# ap33772s.net
KiCad netlist of a schematic drawn in Altium Designer
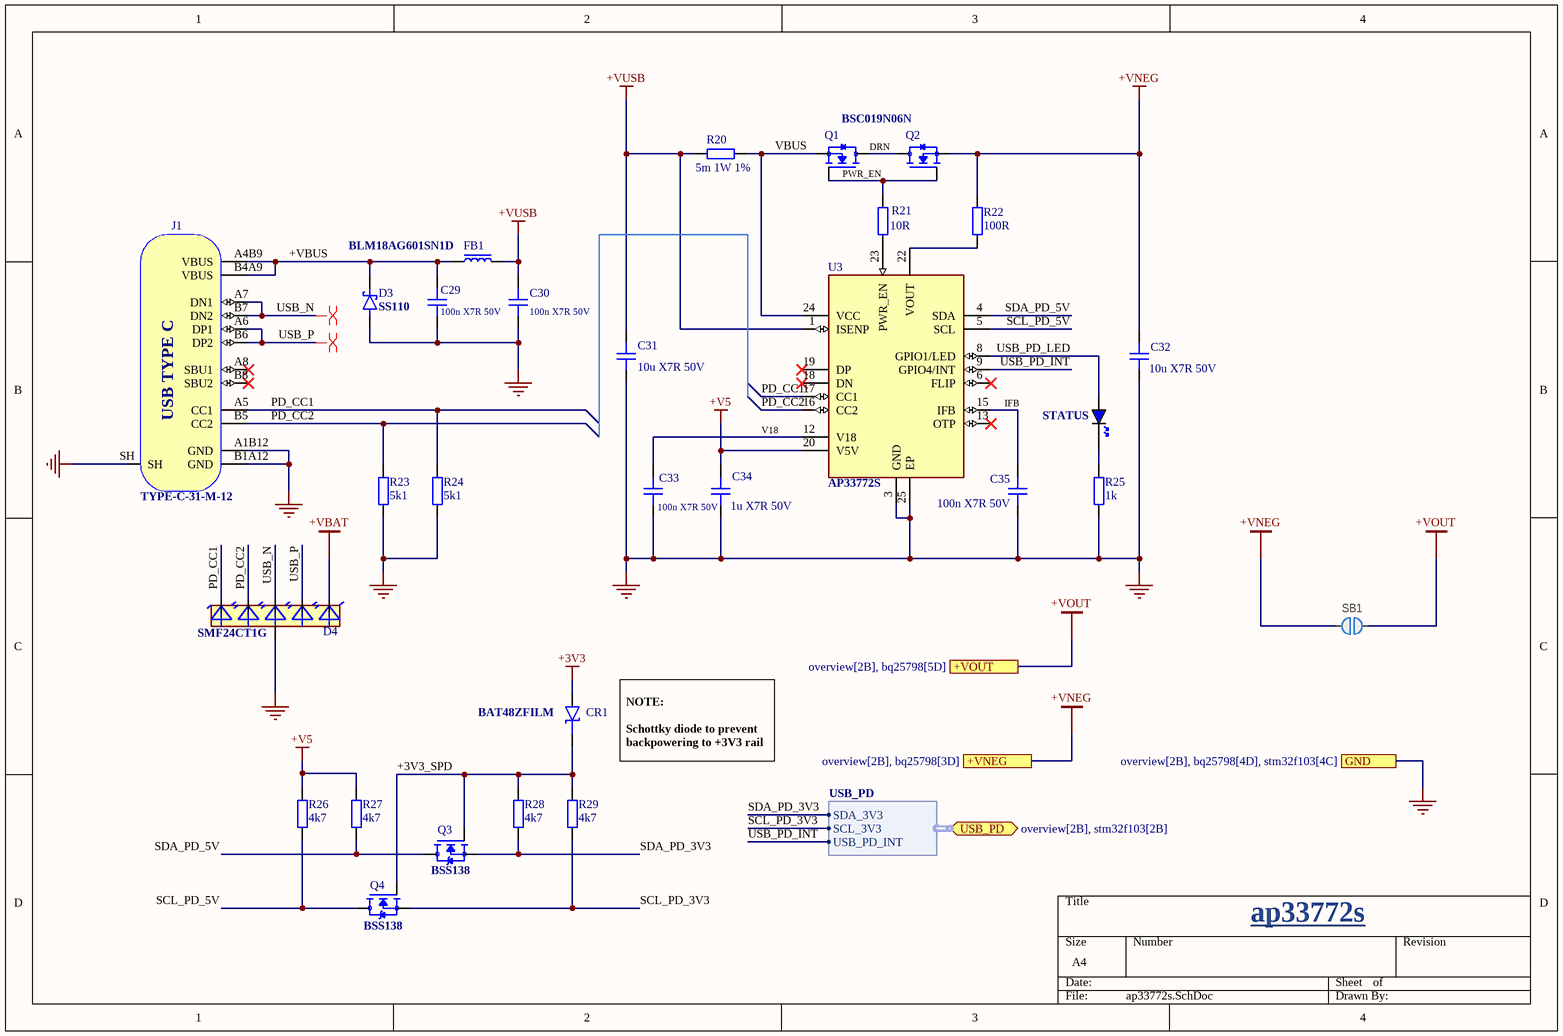
[diagram p0: ap33772s.SchDoc]

(export (version "E")
  (design (tool "Eeschema 10.0.6"))
  (components
    (comp (ref "C29")
      (value "100n X7R 50V")
      (footprint "CAP_0603")
      (description "Capacitor SMD 0603")
      (libsource (lib "Sch_Lib") (part "CAP_0603"))
    )
    (comp (ref "C30")
      (value "100n X7R 50V")
      (footprint "CAP_0603")
      (description "Capacitor SMD 0603")
      (libsource (lib "Sch_Lib") (part "CAP_0603"))
    )
    (comp (ref "C31")
      (value "10u X7R 50V")
      (footprint "CAP_1210")
      (description "Capacitor SMD 1210")
      (libsource (lib "Sch_Lib") (part "CAP_1210"))
    )
    (comp (ref "C32")
      (value "10u X7R 50V")
      (footprint "CAP_1210")
      (description "Capacitor SMD 1210")
      (libsource (lib "Sch_Lib") (part "CAP_1210"))
    )
    (comp (ref "C33")
      (value "100n X7R 50V")
      (footprint "CAP_0603")
      (description "Capacitor SMD 0603")
      (libsource (lib "Sch_Lib") (part "CAP_0603"))
    )
    (comp (ref "C34")
      (value "1u X7R 50V")
      (footprint "CAP_0603")
      (description "Capacitor SMD 0603")
      (libsource (lib "Sch_Lib") (part "CAP_0603"))
    )
    (comp (ref "C35")
      (value "100n X7R 50V")
      (footprint "CAP_0603")
      (description "Capacitor SMD 0603")
      (libsource (lib "Sch_Lib") (part "CAP_0603"))
    )
    (comp (ref "CR1")
      (value "BAT48ZFILM")
      (footprint "*SOD-123_STM")
      (description "Diode Schottky 40 V 350mA (DC) Surface Mount SOD-123")
      (fields (field (name "MF") "STMicroelectronics"))
      (libsource (lib "Sch_Lib") (part "BAT48ZFILM"))
    )
    (comp (ref "D3")
      (value "SS110")
      (footprint "DIOM4325X250N")
      (description "1A, 100V, Schottky Rectifier")
      (fields (field (name "MF") "Taiwan Semiconductor"))
      (libsource (lib "Sch_Lib") (part "SS110"))
    )
    (comp (ref "D4")
      (value "SMF24CT1G")
      (footprint "SOT65P210X110-6N")
      (description "Quint Uni-Directional TVS Diode, 100W, 6-Pin SC-88 ¦ ON Semiconductor SMF24CT1G")
      (fields (field (name "MP") "SMF05C") (field (name "MF") "ProTek Devices"))
      (libsource (lib "Sch_Lib") (part "SMF24CT1G"))
    )
    (comp (ref "FB1")
      (value "BLM18AG601SN1D")
      (footprint "FB_0603")
      (description "Ferrite Bead SMD 0603")
      (libsource (lib "Sch_Lib") (part "FB_0603"))
    )
    (comp (ref "J1")
      (value "TYPE-C-31-M-12")
      (footprint "TYPE-C-31-M-12")
      (description "USB Type C Connector Horizontal SMT")
      (fields (field (name "MANUFACTURER") "Koren Hroparts"))
      (libsource (lib "Sch_Lib") (part "TYPE-C-31-M-12"))
    )
    (comp (ref "Q1")
      (value "BSC019N06N")
      (footprint "BSC014N04LSIATMA1")
      (description "N-Channel 60 V 100A (Ta) 136W (Ta) Surface Mount PG-TDSON-8 FL")
      (fields (field (name "MF") "Infineon") (field (name "MP") "IPD122N10N3 G"))
      (libsource (lib "Sch_Lib") (part "BSC019N06N"))
    )
    (comp (ref "Q2")
      (value "BSC019N06N")
      (footprint "BSC014N04LSIATMA1")
      (description "N-Channel 60 V 100A (Ta) 136W (Ta) Surface Mount PG-TDSON-8 FL")
      (fields (field (name "MF") "Infineon") (field (name "MP") "IPD122N10N3 G"))
      (libsource (lib "Sch_Lib") (part "BSC019N06N"))
    )
    (comp (ref "Q3")
      (value "BSS138")
      (footprint "SOT95P240X111-3N")
      (description "N-Channel 50 V 220mA (Ta) 350mW (Ta) Surface Mount SOT-23-3")
      (fields (field (name "MF") "onsemi"))
      (libsource (lib "Sch_Lib") (part "BSS138"))
    )
    (comp (ref "Q4")
      (value "BSS138")
      (footprint "SOT95P240X111-3N")
      (description "N-Channel 50 V 220mA (Ta) 350mW (Ta) Surface Mount SOT-23-3")
      (fields (field (name "MF") "onsemi"))
      (libsource (lib "Sch_Lib") (part "BSS138"))
    )
    (comp (ref "R20")
      (value "5m 1W 1%")
      (footprint "RES_1206")
      (description "Resistor SMD 1206")
      (libsource (lib "Sch_Lib") (part "RES_1206"))
    )
    (comp (ref "R21")
      (value "10R")
      (footprint "RES_0603")
      (description "Resistor SMD 0603")
      (libsource (lib "Sch_Lib") (part "RES_0603"))
    )
    (comp (ref "R22")
      (value "100R")
      (footprint "RES_0603")
      (description "Resistor SMD 0603")
      (libsource (lib "Sch_Lib") (part "RES_0603"))
    )
    (comp (ref "R23")
      (value "5k1")
      (footprint "RES_0603")
      (description "Resistor SMD 0603")
      (libsource (lib "Schematic-Lib-PhilsLab") (part "RES_0603"))
    )
    (comp (ref "R24")
      (value "5k1")
      (footprint "RES_0603")
      (description "Resistor SMD 0603")
      (libsource (lib "Schematic-Lib-PhilsLab") (part "RES_0603"))
    )
    (comp (ref "R25")
      (value "1k")
      (footprint "RES_0603")
      (description "Resistor SMD 0603")
      (libsource (lib "Schematic-Lib-PhilsLab") (part "RES_0603"))
    )
    (comp (ref "R26")
      (value "4k7")
      (footprint "RES_0603")
      (description "Resistor SMD 0603")
      (libsource (lib "Sch_Lib") (part "RES_0603"))
    )
    (comp (ref "R27")
      (value "4k7")
      (footprint "RES_0603")
      (description "Resistor SMD 0603")
      (libsource (lib "Sch_Lib") (part "RES_0603"))
    )
    (comp (ref "R28")
      (value "4k7")
      (footprint "RES_0603")
      (description "Resistor SMD 0603")
      (libsource (lib "Sch_Lib") (part "RES_0603"))
    )
    (comp (ref "R29")
      (value "4k7")
      (footprint "RES_0603")
      (description "Resistor SMD 0603")
      (libsource (lib "Sch_Lib") (part "RES_0603"))
    )
    (comp (ref "SB1")
      (value "Solderbridge")
      (footprint "Solderbridge")
      (fields (field (name "MANUFACTURER") "N.A.") (field (name "AUTHOR") "rsk"))
      (libsource (lib "Sch_Lib") (part "Solderbridge"))
    )
    (comp (ref "STATUS")
      (value "BLUE")
      (footprint "LED_0603_BLUE")
      (description "LED 0603 BLUE SMD")
      (libsource (lib "Schematic-Lib-PhilsLab") (part "LED_0603_BLUE"))
    )
    (comp (ref "U3")
      (value "AP33772S")
      (footprint "IC_AP33772S")
      (description "USB Controller, PD Sink USB 3.0 USB Interface W-QFN4040-24 (Type A1)")
      (fields (field (name "MF") "Diodes Incorporated") (field (name "MP") "AP33771DKZ-13"))
      (libsource (lib "Sch_Lib") (part "AP33772S"))
    )
  )
  (nets
    (net (code "2") (name "+3V3") (class "Default")
      (node (ref "CR1") (pin "2") (pinfunction "2_2") (pintype "passive"))
    )
    (net (code "3") (name "+V5") (class "Default")
      (node (ref "C34") (pin "2") (pinfunction "2_2") (pintype "passive"))
      (node (ref "R26") (pin "2") (pinfunction "2_2") (pintype "passive"))
      (node (ref "R27") (pin "2") (pinfunction "2_2") (pintype "passive"))
      (node (ref "U3") (pin "20") (pinfunction "V5V_20") (pintype "power_in"))
    )
    (net (code "4") (name "+VBAT") (class "Default")
      (node (ref "D4") (pin "6") (pinfunction "C5_6") (pintype "passive"))
    )
    (net (code "5") (name "+VNEG") (class "Default")
      (node (ref "C32") (pin "2") (pinfunction "2_2") (pintype "passive"))
      (node (ref "Q2") (pin "1") (pinfunction "S_1") (pintype "passive"))
      (node (ref "R22") (pin "2") (pinfunction "2_2") (pintype "passive"))
      (node (ref "SB1") (pin "1") (pinfunction "0_1") (pintype "passive"))
    )
    (net (code "6") (name "+VOUT") (class "Default")
      (node (ref "SB1") (pin "2") (pinfunction "1_2") (pintype "passive"))
    )
    (net (code "7") (name "+VUSB") (class "Default")
      (node (ref "C30") (pin "1") (pinfunction "1_1") (pintype "passive"))
      (node (ref "C31") (pin "2") (pinfunction "2_2") (pintype "passive"))
      (node (ref "FB1") (pin "2") (pinfunction "2_2") (pintype "passive"))
      (node (ref "R20") (pin "1") (pinfunction "1_1") (pintype "passive"))
      (node (ref "U3") (pin "1") (pinfunction "ISENP_1") (pintype "bidirectional"))
    )
    (net (code "8") (name "/+3V3_SPD") (class "Default")
      (node (ref "CR1") (pin "1") (pinfunction "1_1") (pintype "passive"))
      (node (ref "Q3") (pin "1") (pinfunction "G_1") (pintype "passive"))
      (node (ref "Q4") (pin "1") (pinfunction "G_1") (pintype "passive"))
      (node (ref "R28") (pin "2") (pinfunction "2_2") (pintype "passive"))
      (node (ref "R29") (pin "2") (pinfunction "2_2") (pintype "passive"))
    )
    (net (code "9") (name "/+VBUS") (class "Default")
      (node (ref "C29") (pin "1") (pinfunction "1_1") (pintype "passive"))
      (node (ref "D3") (pin "C") (pinfunction "K_C") (pintype "passive"))
      (node (ref "FB1") (pin "1") (pinfunction "1_1") (pintype "passive"))
      (node (ref "J1") (pin "A4B9") (pinfunction "VBUS_A4B9") (pintype "power_in"))
      (node (ref "J1") (pin "B4A9") (pinfunction "VBUS_B4A9") (pintype "power_in"))
    )
    (net (code "10") (name "/DRN") (class "Default")
      (node (ref "Q1") (pin "5") (pinfunction "D_5") (pintype "passive"))
      (node (ref "Q2") (pin "5") (pinfunction "D_5") (pintype "passive"))
    )
    (net (code "11") (name "/IFB") (class "Default")
      (node (ref "C35") (pin "1") (pinfunction "1_1") (pintype "passive"))
      (node (ref "U3") (pin "15") (pinfunction "IFB_15") (pintype "bidirectional"))
    )
    (net (code "12") (name "/PD_CC1") (class "Default")
      (node (ref "D4") (pin "1") (pinfunction "C1_1") (pintype "passive"))
      (node (ref "J1") (pin "A5") (pinfunction "CC1_A5") (pintype "passive"))
      (node (ref "R24") (pin "2") (pinfunction "2_2") (pintype "passive"))
      (node (ref "U3") (pin "17") (pinfunction "CC1_17") (pintype "bidirectional"))
    )
    (net (code "13") (name "/PD_CC2") (class "Default")
      (node (ref "D4") (pin "3") (pinfunction "C2_3") (pintype "passive"))
      (node (ref "J1") (pin "B5") (pinfunction "CC2_B5") (pintype "tri_state"))
      (node (ref "R23") (pin "2") (pinfunction "2_2") (pintype "passive"))
      (node (ref "U3") (pin "16") (pinfunction "CC2_16") (pintype "bidirectional"))
    )
    (net (code "14") (name "/PWR_EN") (class "Default")
      (node (ref "Q1") (pin "4") (pinfunction "G_4") (pintype "passive"))
      (node (ref "Q2") (pin "4") (pinfunction "G_4") (pintype "passive"))
      (node (ref "R21") (pin "2") (pinfunction "2_2") (pintype "passive"))
    )
    (net (code "15") (name "/SCL_PD_3V3") (class "Default")
      (node (ref "Q4") (pin "2") (pinfunction "S_2") (pintype "passive"))
      (node (ref "R29") (pin "1") (pinfunction "1_1") (pintype "passive"))
    )
    (net (code "16") (name "/SCL_PD_5V") (class "Default")
      (node (ref "Q4") (pin "3") (pinfunction "D_3") (pintype "passive"))
      (node (ref "R26") (pin "1") (pinfunction "1_1") (pintype "passive"))
      (node (ref "U3") (pin "5") (pinfunction "SCL_5") (pintype "passive"))
    )
    (net (code "17") (name "/SDA_PD_3V3") (class "Default")
      (node (ref "Q3") (pin "2") (pinfunction "S_2") (pintype "passive"))
      (node (ref "R28") (pin "1") (pinfunction "1_1") (pintype "passive"))
    )
    (net (code "18") (name "/SDA_PD_5V") (class "Default")
      (node (ref "Q3") (pin "3") (pinfunction "D_3") (pintype "passive"))
      (node (ref "R27") (pin "1") (pinfunction "1_1") (pintype "passive"))
      (node (ref "U3") (pin "4") (pinfunction "SDA_4") (pintype "passive"))
    )
    (net (code "19") (name "/USB_N") (class "Default")
      (node (ref "D4") (pin "4") (pinfunction "C3_4") (pintype "passive"))
      (node (ref "J1") (pin "A7") (pinfunction "DN1_A7") (pintype "bidirectional"))
      (node (ref "J1") (pin "B7") (pinfunction "DN2_B7") (pintype "bidirectional"))
    )
    (net (code "20") (name "/USB_P") (class "Default")
      (node (ref "D4") (pin "5") (pinfunction "C4_5") (pintype "passive"))
      (node (ref "J1") (pin "A6") (pinfunction "DP1_A6") (pintype "bidirectional"))
      (node (ref "J1") (pin "B6") (pinfunction "DP2_B6") (pintype "bidirectional"))
    )
    (net (code "21") (name "/USB_PD_INT") (class "Default")
      (node (ref "U3") (pin "9") (pinfunction "GPIO4/INT_9") (pintype "bidirectional"))
    )
    (net (code "22") (name "/USB_PD_LED") (class "Default")
      (node (ref "STATUS") (pin "A") (pinfunction "A_A") (pintype "passive"))
      (node (ref "U3") (pin "8") (pinfunction "GPIO1/LED_8") (pintype "bidirectional"))
    )
    (net (code "23") (name "/V18") (class "Default")
      (node (ref "C33") (pin "1") (pinfunction "1_1") (pintype "passive"))
      (node (ref "U3") (pin "12") (pinfunction "V18_12") (pintype "power_in"))
    )
    (net (code "24") (name "/VBUS") (class "Default")
      (node (ref "Q1") (pin "1") (pinfunction "S_1") (pintype "passive"))
      (node (ref "R20") (pin "2") (pinfunction "2_2") (pintype "passive"))
      (node (ref "U3") (pin "24") (pinfunction "VCC_24") (pintype "power_in"))
    )
    (net (code "26") (name "GND") (class "Default")
      (node (ref "C29") (pin "2") (pinfunction "2_2") (pintype "passive"))
      (node (ref "C30") (pin "2") (pinfunction "2_2") (pintype "passive"))
      (node (ref "C31") (pin "1") (pinfunction "1_1") (pintype "passive"))
      (node (ref "C32") (pin "1") (pinfunction "1_1") (pintype "passive"))
      (node (ref "C33") (pin "2") (pinfunction "2_2") (pintype "passive"))
      (node (ref "C34") (pin "1") (pinfunction "1_1") (pintype "passive"))
      (node (ref "C35") (pin "2") (pinfunction "2_2") (pintype "passive"))
      (node (ref "D3") (pin "A") (pinfunction "A_A") (pintype "passive"))
      (node (ref "D4") (pin "2") (pinfunction "A_2") (pintype "passive"))
      (node (ref "J1") (pin "A1B12") (pinfunction "GND_A1B12") (pintype "power_in"))
      (node (ref "J1") (pin "B1A12") (pinfunction "GND_B1A12") (pintype "power_in"))
      (node (ref "J1") (pin "SH") (pinfunction "SH_SH") (pintype "power_in"))
      (node (ref "R23") (pin "1") (pinfunction "1_1") (pintype "passive"))
      (node (ref "R24") (pin "1") (pinfunction "1_1") (pintype "passive"))
      (node (ref "R25") (pin "2") (pinfunction "2_2") (pintype "passive"))
      (node (ref "U3") (pin "25") (pinfunction "EP_25") (pintype "power_in"))
      (node (ref "U3") (pin "3") (pinfunction "GND_3") (pintype "power_in"))
    )
    (net (code "27") (name "Net-(R25-Pad1)") (class "Default")
      (node (ref "R25") (pin "1") (pinfunction "1_1") (pintype "passive"))
      (node (ref "STATUS") (pin "K") (pinfunction "K_K") (pintype "passive"))
    )
    (net (code "28") (name "Net-(U3-PWR_EN)") (class "Default")
      (node (ref "R21") (pin "1") (pinfunction "1_1") (pintype "passive"))
      (node (ref "U3") (pin "23") (pinfunction "PWR_EN_23") (pintype "input"))
    )
    (net (code "29") (name "Net-(U3-VOUT)") (class "Default")
      (node (ref "R22") (pin "1") (pinfunction "1_1") (pintype "passive"))
      (node (ref "U3") (pin "22") (pinfunction "VOUT_22") (pintype "power_in"))
    )
    (net (code "30") (name "unconnected-(J1-SBU1-PadA8)") (class "Default")
      (node (ref "J1") (pin "A8") (pinfunction "SBU1_A8") (pintype "bidirectional+no_connect"))
    )
    (net (code "31") (name "unconnected-(J1-SBU2-PadB8)") (class "Default")
      (node (ref "J1") (pin "B8") (pinfunction "SBU2_B8") (pintype "bidirectional+no_connect"))
    )
    (net (code "32") (name "unconnected-(U3-DN-Pad18)") (class "Default")
      (node (ref "U3") (pin "18") (pinfunction "DN_18") (pintype "passive+no_connect"))
    )
    (net (code "33") (name "unconnected-(U3-DP-Pad19)") (class "Default")
      (node (ref "U3") (pin "19") (pinfunction "DP_19") (pintype "passive+no_connect"))
    )
    (net (code "34") (name "unconnected-(U3-FLIP-Pad6)") (class "Default")
      (node (ref "U3") (pin "6") (pinfunction "FLIP_6") (pintype "bidirectional+no_connect"))
    )
    (net (code "35") (name "unconnected-(U3-OTP-Pad13)") (class "Default")
      (node (ref "U3") (pin "13") (pinfunction "OTP_13") (pintype "bidirectional+no_connect"))
    )
  )
)
